# LED-Board_long.net
KiCad netlist of a schematic drawn in EAGLE
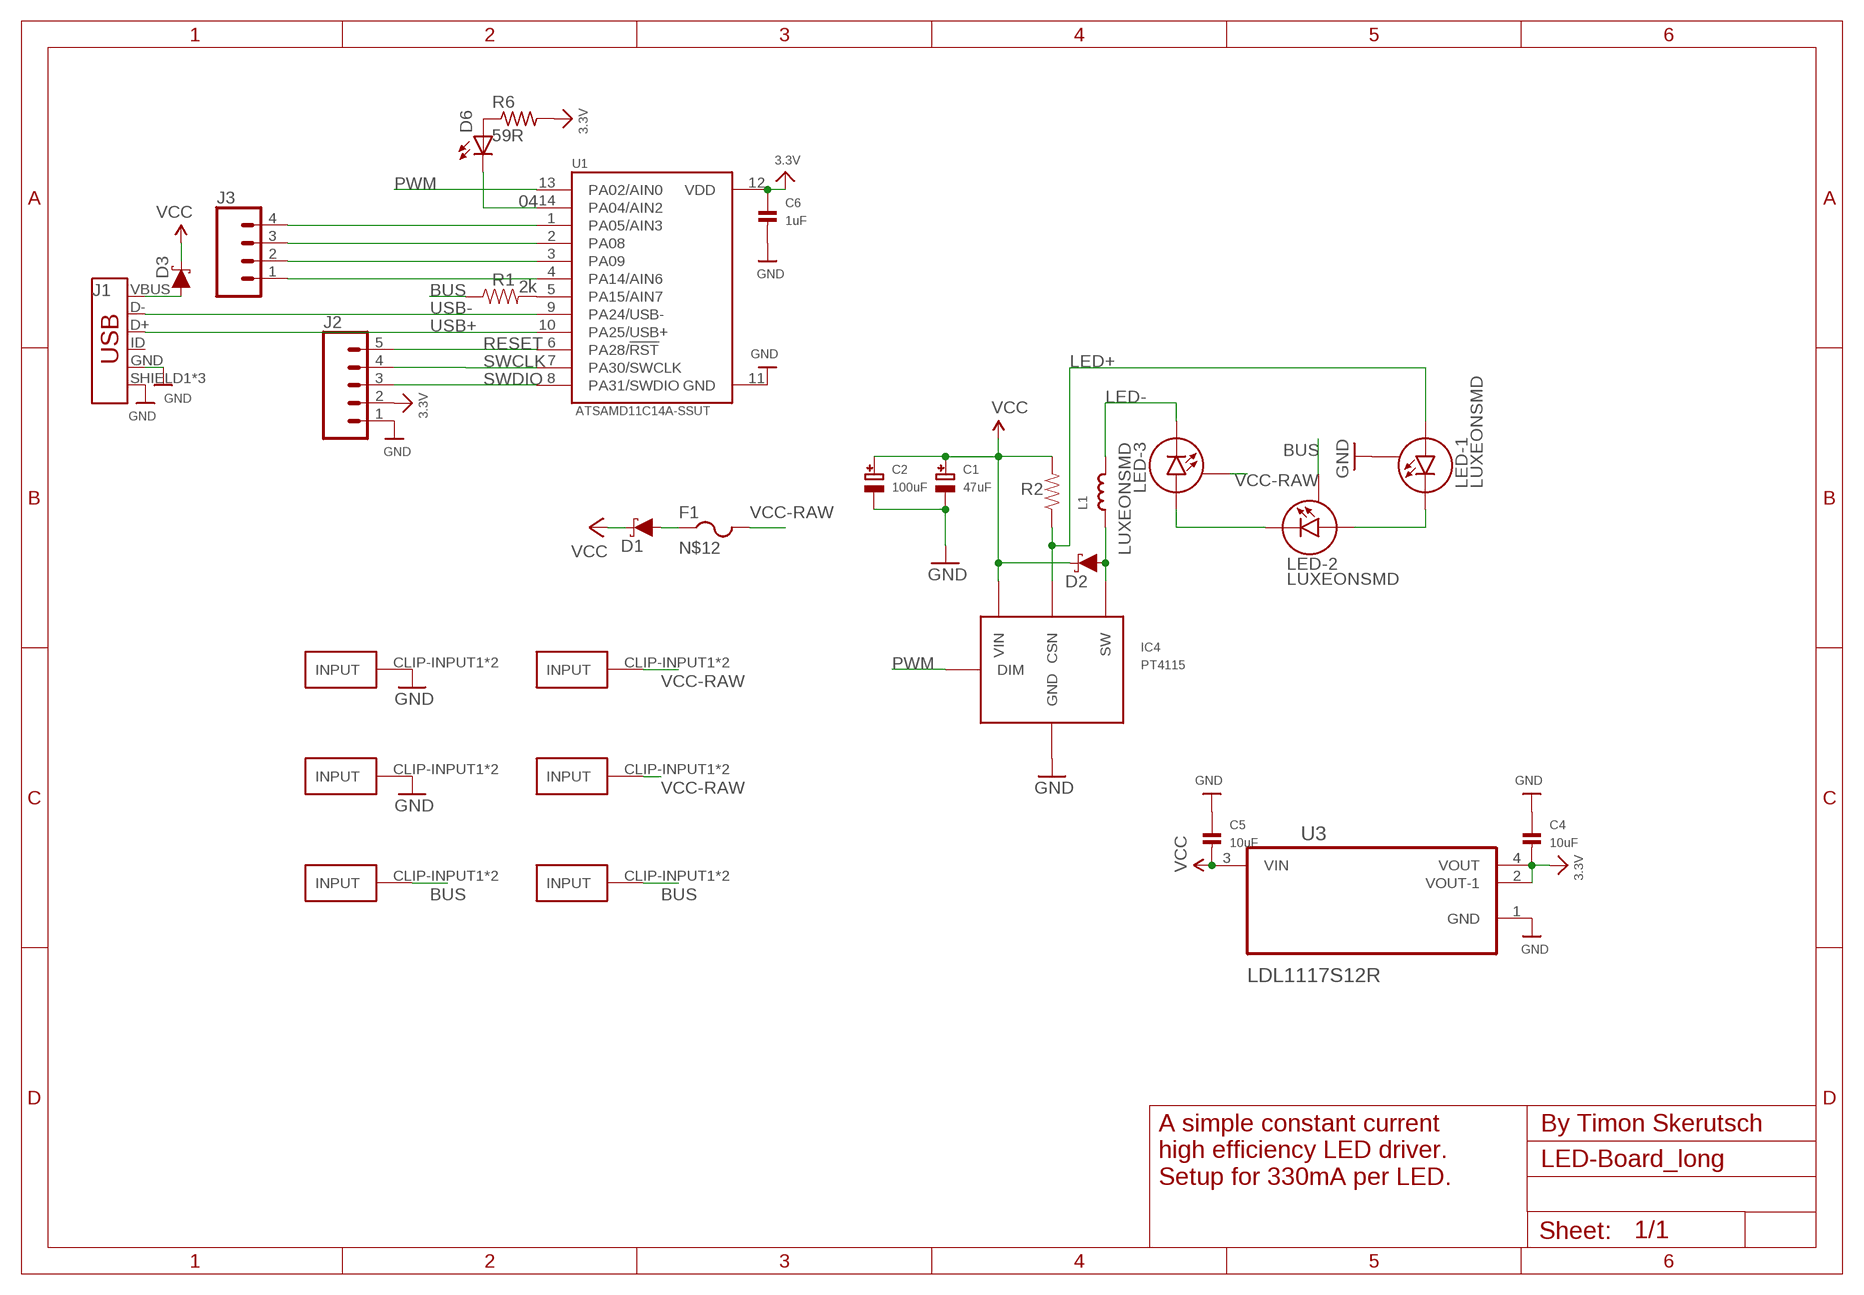
[diagram p0: schematic, sheet 1]

(export (version "E")
  (design (tool "Eeschema 10.0.6"))
  (components
    (comp (ref "C1")
      (value "47uF")
      (footprint "eagle-import:PANASONIC_D")
      (libsource (lib "eagle-import") (part "CAP_ELECTROLYTICPANASONIC_D"))
    )
    (comp (ref "C2")
      (value "100uF")
      (footprint "eagle-import:PANASONIC_D")
      (libsource (lib "eagle-import") (part "CAP_ELECTROLYTICPANASONIC_D"))
    )
    (comp (ref "C4")
      (value "10uF")
      (footprint "eagle-import:0805")
      (libsource (lib "eagle-import") (part "CAP_CERAMIC0805"))
    )
    (comp (ref "C5")
      (value "10uF")
      (footprint "eagle-import:0603")
      (libsource (lib "eagle-import") (part "CAP_CERAMIC0603"))
    )
    (comp (ref "C6")
      (value "1uF")
      (footprint "eagle-import:0603")
      (libsource (lib "eagle-import") (part "CAP_CERAMIC0603"))
    )
    (comp (ref "D1")
      (value "3A/40V/500mV")
      (footprint "eagle-import:SMA-DIODE")
      (libsource (lib "eagle-import") (part "DIODE-SCHOTTKY-B340A"))
    )
    (comp (ref "D2")
      (value "3A/40V/500mV")
      (footprint "eagle-import:SMA-DIODE")
      (libsource (lib "eagle-import") (part "DIODE-SCHOTTKY-B340A"))
    )
    (comp (ref "D3")
      (value "3A/40V/500mV")
      (footprint "eagle-import:SMA-DIODE")
      (libsource (lib "eagle-import") (part "DIODE-SCHOTTKY-B340A"))
    )
    (comp (ref "D6")
      (value "LEDCHIPLED_0805")
      (footprint "eagle-import:CHIPLED_0805")
      (libsource (lib "eagle-import") (part "LEDCHIPLED_0805"))
    )
    (comp (ref "F1")
      (value "TLC-MSMD110/24")
      (footprint "eagle-import:1812")
      (libsource (lib "eagle-import") (part "PTCFUSE-1812"))
    )
    (comp (ref "GND-CLIP")
      (value "FUSE-HOLDER-5X20MM")
      (footprint "eagle-import:FUSE-HOLDER-5X20MM")
      (libsource (lib "eagle-import") (part "FUSE-HOLDER-5X20MM"))
    )
    (comp (ref "GND-CLIP3")
      (value "FUSE-HOLDER-5X20MM")
      (footprint "eagle-import:FUSE-HOLDER-5X20MM")
      (libsource (lib "eagle-import") (part "FUSE-HOLDER-5X20MM"))
    )
    (comp (ref "IC4")
      (value "PT4115")
      (footprint "eagle-import:PT4115")
      (libsource (lib "eagle-import") (part "PT4115"))
    )
    (comp (ref "J1")
      (value "USB_MICRO-B_FEMALE-SMT")
      (footprint "eagle-import:USB-B-MICRO-SMD")
      (libsource (lib "eagle-import") (part "USB_MICRO-B_FEMALE-SMT"))
    )
    (comp (ref "J2")
      (value "CONN_05")
      (footprint "eagle-import:1X05")
      (libsource (lib "eagle-import") (part "CONN_05"))
    )
    (comp (ref "J3")
      (value "CONN_04")
      (footprint "eagle-import:1X04")
      (libsource (lib "eagle-import") (part "CONN_04"))
    )
    (comp (ref "L1")
      (value "INDUCTORTDK_VLC6045")
      (footprint "eagle-import:INDUCTOR_6X6MM_TDK_VLC6045")
      (libsource (lib "eagle-import") (part "INDUCTORTDK_VLC6045"))
    )
    (comp (ref "LED-1")
      (value "LUXEONSMD")
      (footprint "eagle-import:LUXEON")
      (libsource (lib "eagle-import") (part "LUXEONSMD"))
    )
    (comp (ref "LED-2")
      (value "LUXEONSMD")
      (footprint "eagle-import:LUXEON")
      (libsource (lib "eagle-import") (part "LUXEONSMD"))
    )
    (comp (ref "LED-3")
      (value "LUXEONSMD")
      (footprint "eagle-import:LUXEON")
      (libsource (lib "eagle-import") (part "LUXEONSMD"))
    )
    (comp (ref "PWM-CLIP")
      (value "FUSE-HOLDER-5X20MM")
      (footprint "eagle-import:FUSE-HOLDER-5X20MM")
      (libsource (lib "eagle-import") (part "FUSE-HOLDER-5X20MM"))
    )
    (comp (ref "PWM-CLIP1")
      (value "FUSE-HOLDER-5X20MM")
      (footprint "eagle-import:FUSE-HOLDER-5X20MM")
      (libsource (lib "eagle-import") (part "FUSE-HOLDER-5X20MM"))
    )
    (comp (ref "R1")
      (value "2k")
      (footprint "eagle-import:1206")
      (libsource (lib "eagle-import") (part "RESISTOR1206"))
    )
    (comp (ref "R2")
      (value "0.3")
      (footprint "eagle-import:1206")
      (libsource (lib "eagle-import") (part "RESISTOR1206"))
    )
    (comp (ref "R6")
      (value "59R")
      (footprint "eagle-import:R0805")
      (libsource (lib "eagle-import") (part "R-US_R0805"))
    )
    (comp (ref "U1")
      (value "ATSAMD11C14A-SSUT")
      (footprint "eagle-import:SOIC127P600X160-14N")
      (fields (field (name "MF") "Microchip"))
      (libsource (lib "eagle-import") (part "ATSAMD11C14A-SSUT"))
    )
    (comp (ref "U3")
      (value "LDL1117S12R")
      (footprint "eagle-import:SOT230P700X180-4N")
      (fields (field (name "MF") "STMicroelectronics"))
      (libsource (lib "eagle-import") (part "LDL1117S12R"))
    )
    (comp (ref "VCC-CLIP")
      (value "FUSE-HOLDER-5X20MM")
      (footprint "eagle-import:FUSE-HOLDER-5X20MM")
      (libsource (lib "eagle-import") (part "FUSE-HOLDER-5X20MM"))
    )
    (comp (ref "VCC-CLIP3")
      (value "FUSE-HOLDER-5X20MM")
      (footprint "eagle-import:FUSE-HOLDER-5X20MM")
      (libsource (lib "eagle-import") (part "FUSE-HOLDER-5X20MM"))
    )
  )
  (nets
    (net (code "1") (name "/04") (class "Default")
      (node (ref "D6") (pin "C") (pinfunction "C_C") (pintype "passive"))
      (node (ref "U1") (pin "14") (pinfunction "PA04/AIN2_14") (pintype "bidirectional"))
    )
    (net (code "2") (name "/BUS") (class "Default")
      (node (ref "LED-2") (pin "S") (pinfunction "S_S") (pintype "bidirectional"))
      (node (ref "PWM-CLIP") (pin "CLIP-INPUT1") (pinfunction "INPUT_CLIP-INPUT1") (pintype "bidirectional"))
      (node (ref "PWM-CLIP") (pin "CLIP-INPUT2") (pinfunction "INPUT_CLIP-INPUT2") (pintype "bidirectional"))
      (node (ref "PWM-CLIP1") (pin "CLIP-INPUT1") (pinfunction "INPUT_CLIP-INPUT1") (pintype "bidirectional"))
      (node (ref "PWM-CLIP1") (pin "CLIP-INPUT2") (pinfunction "INPUT_CLIP-INPUT2") (pintype "bidirectional"))
      (node (ref "R1") (pin "1") (pinfunction "1_1") (pintype "passive"))
    )
    (net (code "3") (name "/LED+") (class "Default")
      (node (ref "IC4") (pin "4") (pinfunction "CSN_4") (pintype "bidirectional"))
      (node (ref "LED-1") (pin "A") (pinfunction "A_A") (pintype "passive"))
      (node (ref "R2") (pin "1") (pinfunction "1_1") (pintype "passive"))
    )
    (net (code "4") (name "/LED-") (class "Default")
      (node (ref "L1") (pin "P$2") (pinfunction "2_P$2") (pintype "passive"))
      (node (ref "LED-3") (pin "C") (pinfunction "C_C") (pintype "passive"))
    )
    (net (code "5") (name "/N$12") (class "Default")
      (node (ref "D1") (pin "A") (pinfunction "A_A") (pintype "passive"))
      (node (ref "F1") (pin "1") (pinfunction "1_1") (pintype "passive"))
    )
    (net (code "6") (name "/PWM") (class "Default")
      (node (ref "IC4") (pin "3") (pinfunction "DIM_3") (pintype "bidirectional"))
      (node (ref "U1") (pin "13") (pinfunction "PA02/AIN0_13") (pintype "bidirectional"))
    )
    (net (code "7") (name "/RESET") (class "Default")
      (node (ref "J2") (pin "5") (pinfunction "5_5") (pintype "passive"))
      (node (ref "U1") (pin "6") (pinfunction "PA28/~{RST}_6") (pintype "bidirectional"))
    )
    (net (code "8") (name "/SWCLK") (class "Default")
      (node (ref "J2") (pin "4") (pinfunction "4_4") (pintype "passive"))
      (node (ref "U1") (pin "7") (pinfunction "PA30/SWCLK_7") (pintype "bidirectional"))
    )
    (net (code "9") (name "/SWDIO") (class "Default")
      (node (ref "J2") (pin "3") (pinfunction "3_3") (pintype "passive"))
      (node (ref "U1") (pin "8") (pinfunction "PA31/SWDIO_8") (pintype "bidirectional"))
    )
    (net (code "10") (name "/USB+") (class "Default")
      (node (ref "J1") (pin "D+") (pinfunction "D+_D+") (pintype "bidirectional"))
      (node (ref "U1") (pin "10") (pinfunction "PA25/USB+_10") (pintype "bidirectional"))
    )
    (net (code "11") (name "/USB-") (class "Default")
      (node (ref "J1") (pin "D-") (pinfunction "D-_D-") (pintype "bidirectional"))
      (node (ref "U1") (pin "9") (pinfunction "PA24/USB-_9") (pintype "bidirectional"))
    )
    (net (code "12") (name "/VCC-RAW") (class "Default")
      (node (ref "F1") (pin "2") (pinfunction "2_2") (pintype "passive"))
      (node (ref "LED-3") (pin "S") (pinfunction "S_S") (pintype "bidirectional"))
      (node (ref "VCC-CLIP") (pin "CLIP-INPUT1") (pinfunction "INPUT_CLIP-INPUT1") (pintype "bidirectional"))
      (node (ref "VCC-CLIP") (pin "CLIP-INPUT2") (pinfunction "INPUT_CLIP-INPUT2") (pintype "bidirectional"))
      (node (ref "VCC-CLIP3") (pin "CLIP-INPUT1") (pinfunction "INPUT_CLIP-INPUT1") (pintype "bidirectional"))
      (node (ref "VCC-CLIP3") (pin "CLIP-INPUT2") (pinfunction "INPUT_CLIP-INPUT2") (pintype "bidirectional"))
    )
    (net (code "13") (name "3.3V") (class "Default")
      (node (ref "C4") (pin "2") (pinfunction "P$2_2") (pintype "passive"))
      (node (ref "C6") (pin "1") (pinfunction "P$1_1") (pintype "passive"))
      (node (ref "J2") (pin "2") (pinfunction "2_2") (pintype "passive"))
      (node (ref "R6") (pin "2") (pinfunction "2_2") (pintype "passive"))
      (node (ref "U1") (pin "12") (pinfunction "VDD_12") (pintype "power_in"))
      (node (ref "U3") (pin "2") (pinfunction "VOUT-1_2") (pintype "output"))
      (node (ref "U3") (pin "4") (pinfunction "VOUT_4") (pintype "output"))
    )
    (net (code "14") (name "GND") (class "Default")
      (node (ref "C1") (pin "-") (pinfunction "-_-") (pintype "passive"))
      (node (ref "C2") (pin "-") (pinfunction "-_-") (pintype "passive"))
      (node (ref "C4") (pin "1") (pinfunction "P$1_1") (pintype "passive"))
      (node (ref "C5") (pin "1") (pinfunction "P$1_1") (pintype "passive"))
      (node (ref "C6") (pin "2") (pinfunction "P$2_2") (pintype "passive"))
      (node (ref "GND-CLIP") (pin "CLIP-INPUT1") (pinfunction "INPUT_CLIP-INPUT1") (pintype "bidirectional"))
      (node (ref "GND-CLIP") (pin "CLIP-INPUT2") (pinfunction "INPUT_CLIP-INPUT2") (pintype "bidirectional"))
      (node (ref "GND-CLIP3") (pin "CLIP-INPUT1") (pinfunction "INPUT_CLIP-INPUT1") (pintype "bidirectional"))
      (node (ref "GND-CLIP3") (pin "CLIP-INPUT2") (pinfunction "INPUT_CLIP-INPUT2") (pintype "bidirectional"))
      (node (ref "IC4") (pin "2") (pinfunction "GND_2") (pintype "power_in"))
      (node (ref "IC4") (pin "2A") (pinfunction "GND_2A") (pintype "power_in"))
      (node (ref "J1") (pin "GND") (pinfunction "GND_GND") (pintype "power_in"))
      (node (ref "J1") (pin "SHIELD1") (pinfunction "SHIELD_SHIELD1") (pintype "bidirectional"))
      (node (ref "J1") (pin "SHIELD2") (pinfunction "SHIELD_SHIELD2") (pintype "bidirectional"))
      (node (ref "J1") (pin "SHIELD3") (pinfunction "SHIELD_SHIELD3") (pintype "bidirectional"))
      (node (ref "J2") (pin "1") (pinfunction "1_1") (pintype "passive"))
      (node (ref "LED-1") (pin "S") (pinfunction "S_S") (pintype "bidirectional"))
      (node (ref "U1") (pin "11") (pinfunction "GND_11") (pintype "power_in"))
      (node (ref "U3") (pin "1") (pinfunction "GND_1") (pintype "power_in"))
    )
    (net (code "15") (name "Net-(D3-PadA)") (class "Default")
      (node (ref "D3") (pin "A") (pinfunction "A_A") (pintype "passive"))
      (node (ref "J1") (pin "VBUS") (pinfunction "VBUS_VBUS") (pintype "power_in"))
    )
    (net (code "16") (name "Net-(D6-PadA)") (class "Default")
      (node (ref "D6") (pin "A") (pinfunction "A_A") (pintype "passive"))
      (node (ref "R6") (pin "1") (pinfunction "1_1") (pintype "passive"))
    )
    (net (code "17") (name "Net-(IC4-SW)") (class "Default")
      (node (ref "D2") (pin "A") (pinfunction "A_A") (pintype "passive"))
      (node (ref "IC4") (pin "1") (pinfunction "SW_1") (pintype "bidirectional"))
      (node (ref "L1") (pin "P$1") (pinfunction "1_P$1") (pintype "passive"))
    )
    (net (code "18") (name "Net-(LED-1-PadC)") (class "Default")
      (node (ref "LED-1") (pin "C") (pinfunction "C_C") (pintype "passive"))
      (node (ref "LED-2") (pin "A") (pinfunction "A_A") (pintype "passive"))
    )
    (net (code "19") (name "Net-(LED-2-PadC)") (class "Default")
      (node (ref "LED-2") (pin "C") (pinfunction "C_C") (pintype "passive"))
      (node (ref "LED-3") (pin "A") (pinfunction "A_A") (pintype "passive"))
    )
    (net (code "20") (name "Net-(U1-PA05{slash}AIN3)") (class "Default")
      (node (ref "J3") (pin "4") (pinfunction "4_4") (pintype "passive"))
      (node (ref "U1") (pin "1") (pinfunction "PA05/AIN3_1") (pintype "bidirectional"))
    )
    (net (code "21") (name "Net-(U1-PA08)") (class "Default")
      (node (ref "J3") (pin "3") (pinfunction "3_3") (pintype "passive"))
      (node (ref "U1") (pin "2") (pinfunction "PA08_2") (pintype "bidirectional"))
    )
    (net (code "22") (name "Net-(U1-PA09)") (class "Default")
      (node (ref "J3") (pin "2") (pinfunction "2_2") (pintype "passive"))
      (node (ref "U1") (pin "3") (pinfunction "PA09_3") (pintype "bidirectional"))
    )
    (net (code "23") (name "Net-(U1-PA14{slash}AIN6)") (class "Default")
      (node (ref "J3") (pin "1") (pinfunction "1_1") (pintype "passive"))
      (node (ref "U1") (pin "4") (pinfunction "PA14/AIN6_4") (pintype "bidirectional"))
    )
    (net (code "24") (name "Net-(U1-PA15{slash}AIN7)") (class "Default")
      (node (ref "R1") (pin "2") (pinfunction "2_2") (pintype "passive"))
      (node (ref "U1") (pin "5") (pinfunction "PA15/AIN7_5") (pintype "bidirectional"))
    )
    (net (code "25") (name "VCC") (class "Default")
      (node (ref "C1") (pin "+") (pinfunction "+_+") (pintype "passive"))
      (node (ref "C2") (pin "+") (pinfunction "+_+") (pintype "passive"))
      (node (ref "C5") (pin "2") (pinfunction "P$2_2") (pintype "passive"))
      (node (ref "D1") (pin "C") (pinfunction "C_C") (pintype "passive"))
      (node (ref "D2") (pin "C") (pinfunction "C_C") (pintype "passive"))
      (node (ref "D3") (pin "C") (pinfunction "C_C") (pintype "passive"))
      (node (ref "IC4") (pin "5") (pinfunction "VIN_5") (pintype "bidirectional"))
      (node (ref "R2") (pin "2") (pinfunction "2_2") (pintype "passive"))
      (node (ref "U3") (pin "3") (pinfunction "VIN_3") (pintype "input"))
    )
    (net (code "26") (name "unconnected-(J1-PadID)") (class "Default")
      (node (ref "J1") (pin "ID") (pinfunction "ID_ID") (pintype "bidirectional"))
    )
  )
)
